# lumVoiture.net
KiCad netlist of a schematic drawn in EAGLE
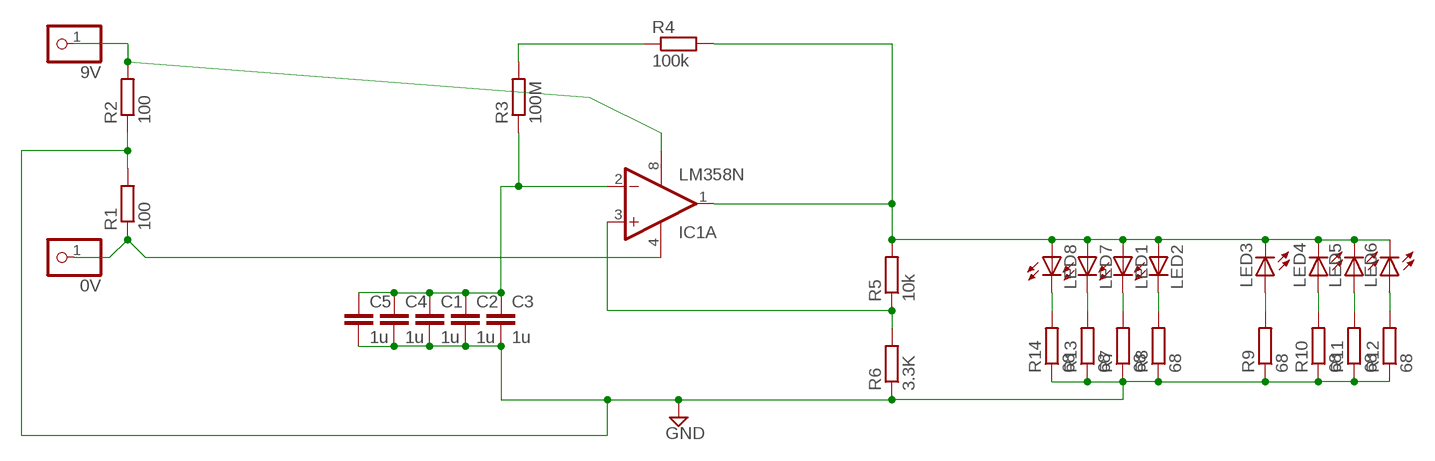
[diagram p0: schematic, sheet 1]

(export (version "E")
  (design (tool "Eeschema 10.0.6"))
  (components
    (comp (ref "0V")
      (value "PINHD-1X1")
      (footprint "eagle-import:1X01")
      (libsource (lib "eagle-import") (part "PINHD-1X1"))
    )
    (comp (ref "9V")
      (value "PINHD-1X1")
      (footprint "eagle-import:1X01")
      (libsource (lib "eagle-import") (part "PINHD-1X1"))
    )
    (comp (ref "C1")
      (value "1u")
      (footprint "eagle-import:C025-025X050")
      (libsource (lib "eagle-import") (part "C-EU025-025X050"))
    )
    (comp (ref "C2")
      (value "1u")
      (footprint "eagle-import:C025-025X050")
      (libsource (lib "eagle-import") (part "C-EU025-025X050"))
    )
    (comp (ref "C3")
      (value "1u")
      (footprint "eagle-import:C025-025X050")
      (libsource (lib "eagle-import") (part "C-EU025-025X050"))
    )
    (comp (ref "C4")
      (value "1u")
      (footprint "eagle-import:C025-025X050")
      (libsource (lib "eagle-import") (part "C-EU025-025X050"))
    )
    (comp (ref "C5")
      (value "1u")
      (footprint "eagle-import:C025-025X050")
      (libsource (lib "eagle-import") (part "C-EU025-025X050"))
    )
    (comp (ref "IC1")
      (value "LM358N")
      (footprint "eagle-import:DIL08")
      (libsource (lib "eagle-import") (part "LM358N"))
    )
    (comp (ref "LED1")
      (value "LED5MM")
      (footprint "eagle-import:LED5MM")
      (libsource (lib "eagle-import") (part "LED5MM"))
    )
    (comp (ref "LED2")
      (value "LED5MM")
      (footprint "eagle-import:LED5MM")
      (libsource (lib "eagle-import") (part "LED5MM"))
    )
    (comp (ref "LED3")
      (value "LED5MM")
      (footprint "eagle-import:LED5MM")
      (libsource (lib "eagle-import") (part "LED5MM"))
    )
    (comp (ref "LED4")
      (value "LED5MM")
      (footprint "eagle-import:LED5MM")
      (libsource (lib "eagle-import") (part "LED5MM"))
    )
    (comp (ref "LED5")
      (value "LED5MM")
      (footprint "eagle-import:LED5MM")
      (libsource (lib "eagle-import") (part "LED5MM"))
    )
    (comp (ref "LED6")
      (value "LED5MM")
      (footprint "eagle-import:LED5MM")
      (libsource (lib "eagle-import") (part "LED5MM"))
    )
    (comp (ref "LED7")
      (value "LED5MM")
      (footprint "eagle-import:LED5MM")
      (libsource (lib "eagle-import") (part "LED5MM"))
    )
    (comp (ref "LED8")
      (value "LED5MM")
      (footprint "eagle-import:LED5MM")
      (libsource (lib "eagle-import") (part "LED5MM"))
    )
    (comp (ref "R1")
      (value "100")
      (footprint "eagle-import:0207_10")
      (libsource (lib "eagle-import") (part "R-EU_0207/10"))
    )
    (comp (ref "R2")
      (value "100")
      (footprint "eagle-import:0207_10")
      (libsource (lib "eagle-import") (part "R-EU_0207/10"))
    )
    (comp (ref "R3")
      (value "100M")
      (footprint "eagle-import:0207_10")
      (libsource (lib "eagle-import") (part "R-EU_0207/10"))
    )
    (comp (ref "R4")
      (value "100k")
      (footprint "eagle-import:0207_10")
      (libsource (lib "eagle-import") (part "R-EU_0207/10"))
    )
    (comp (ref "R5")
      (value "10k")
      (footprint "eagle-import:0207_10")
      (libsource (lib "eagle-import") (part "R-EU_0207/10"))
    )
    (comp (ref "R6")
      (value "3.3K")
      (footprint "eagle-import:0207_10")
      (libsource (lib "eagle-import") (part "R-EU_0207/10"))
    )
    (comp (ref "R7")
      (value "68")
      (footprint "eagle-import:0207_10")
      (libsource (lib "eagle-import") (part "R-EU_0207/10"))
    )
    (comp (ref "R8")
      (value "68")
      (footprint "eagle-import:0207_10")
      (libsource (lib "eagle-import") (part "R-EU_0207/10"))
    )
    (comp (ref "R9")
      (value "68")
      (footprint "eagle-import:0207_10")
      (libsource (lib "eagle-import") (part "R-EU_0207/10"))
    )
    (comp (ref "R10")
      (value "68")
      (footprint "eagle-import:0207_10")
      (libsource (lib "eagle-import") (part "R-EU_0207/10"))
    )
    (comp (ref "R11")
      (value "68")
      (footprint "eagle-import:0207_10")
      (libsource (lib "eagle-import") (part "R-EU_0207/10"))
    )
    (comp (ref "R12")
      (value "68")
      (footprint "eagle-import:0207_10")
      (libsource (lib "eagle-import") (part "R-EU_0207/10"))
    )
    (comp (ref "R13")
      (value "68")
      (footprint "eagle-import:0207_10")
      (libsource (lib "eagle-import") (part "R-EU_0207/10"))
    )
    (comp (ref "R14")
      (value "68")
      (footprint "eagle-import:0207_10")
      (libsource (lib "eagle-import") (part "R-EU_0207/10"))
    )
  )
  (nets
    (net (code "1") (name "GND") (class "Default")
      (node (ref "C1") (pin "2") (pinfunction "2_2") (pintype "passive"))
      (node (ref "C2") (pin "2") (pinfunction "2_2") (pintype "passive"))
      (node (ref "C3") (pin "2") (pinfunction "2_2") (pintype "passive"))
      (node (ref "C4") (pin "2") (pinfunction "2_2") (pintype "passive"))
      (node (ref "C5") (pin "2") (pinfunction "2_2") (pintype "passive"))
      (node (ref "R1") (pin "2") (pinfunction "2_2") (pintype "passive"))
      (node (ref "R10") (pin "1") (pinfunction "1_1") (pintype "passive"))
      (node (ref "R11") (pin "1") (pinfunction "1_1") (pintype "passive"))
      (node (ref "R12") (pin "1") (pinfunction "1_1") (pintype "passive"))
      (node (ref "R13") (pin "1") (pinfunction "1_1") (pintype "passive"))
      (node (ref "R14") (pin "1") (pinfunction "1_1") (pintype "passive"))
      (node (ref "R2") (pin "1") (pinfunction "1_1") (pintype "passive"))
      (node (ref "R6") (pin "1") (pinfunction "1_1") (pintype "passive"))
      (node (ref "R7") (pin "1") (pinfunction "1_1") (pintype "passive"))
      (node (ref "R8") (pin "1") (pinfunction "1_1") (pintype "passive"))
      (node (ref "R9") (pin "1") (pinfunction "1_1") (pintype "passive"))
    )
    (net (code "2") (name "Net-(IC1A-+IN)") (class "Default")
      (node (ref "IC1") (pin "3") (pinfunction "+IN_3") (pintype "input"))
      (node (ref "R5") (pin "1") (pinfunction "1_1") (pintype "passive"))
      (node (ref "R6") (pin "2") (pinfunction "2_2") (pintype "passive"))
    )
    (net (code "3") (name "Net-(IC1A--IN)") (class "Default")
      (node (ref "C1") (pin "1") (pinfunction "1_1") (pintype "passive"))
      (node (ref "C2") (pin "1") (pinfunction "1_1") (pintype "passive"))
      (node (ref "C3") (pin "1") (pinfunction "1_1") (pintype "passive"))
      (node (ref "C4") (pin "1") (pinfunction "1_1") (pintype "passive"))
      (node (ref "C5") (pin "1") (pinfunction "1_1") (pintype "passive"))
      (node (ref "IC1") (pin "2") (pinfunction "-IN_2") (pintype "input"))
      (node (ref "R3") (pin "1") (pinfunction "1_1") (pintype "passive"))
    )
    (net (code "4") (name "Net-(IC1A-OUT)") (class "Default")
      (node (ref "IC1") (pin "1") (pinfunction "OUT_1") (pintype "output"))
      (node (ref "LED1") (pin "A") (pinfunction "A_A") (pintype "passive"))
      (node (ref "LED2") (pin "A") (pinfunction "A_A") (pintype "passive"))
      (node (ref "LED3") (pin "K") (pinfunction "C_K") (pintype "passive"))
      (node (ref "LED4") (pin "K") (pinfunction "C_K") (pintype "passive"))
      (node (ref "LED5") (pin "K") (pinfunction "C_K") (pintype "passive"))
      (node (ref "LED6") (pin "K") (pinfunction "C_K") (pintype "passive"))
      (node (ref "LED7") (pin "A") (pinfunction "A_A") (pintype "passive"))
      (node (ref "LED8") (pin "A") (pinfunction "A_A") (pintype "passive"))
      (node (ref "R4") (pin "2") (pinfunction "2_2") (pintype "passive"))
      (node (ref "R5") (pin "2") (pinfunction "2_2") (pintype "passive"))
    )
    (net (code "5") (name "Net-(IC1C-V+)") (class "Default")
      (node (ref "9V") (pin "1") (pinfunction "1_1") (pintype "passive"))
      (node (ref "IC1") (pin "8") (pinfunction "V+_8") (pintype "power_in"))
      (node (ref "R2") (pin "2") (pinfunction "2_2") (pintype "passive"))
    )
    (net (code "6") (name "Net-(IC1C-V-)") (class "Default")
      (node (ref "0V") (pin "1") (pinfunction "1_1") (pintype "passive"))
      (node (ref "IC1") (pin "4") (pinfunction "V-_4") (pintype "power_in"))
      (node (ref "R1") (pin "1") (pinfunction "1_1") (pintype "passive"))
    )
    (net (code "7") (name "Net-(LED1-C)") (class "Default")
      (node (ref "LED1") (pin "K") (pinfunction "C_K") (pintype "passive"))
      (node (ref "R7") (pin "2") (pinfunction "2_2") (pintype "passive"))
    )
    (net (code "8") (name "Net-(LED2-C)") (class "Default")
      (node (ref "LED2") (pin "K") (pinfunction "C_K") (pintype "passive"))
      (node (ref "R8") (pin "2") (pinfunction "2_2") (pintype "passive"))
    )
    (net (code "9") (name "Net-(LED3-PadA)") (class "Default")
      (node (ref "LED3") (pin "A") (pinfunction "A_A") (pintype "passive"))
      (node (ref "R9") (pin "2") (pinfunction "2_2") (pintype "passive"))
    )
    (net (code "10") (name "Net-(LED4-PadA)") (class "Default")
      (node (ref "LED4") (pin "A") (pinfunction "A_A") (pintype "passive"))
      (node (ref "R10") (pin "2") (pinfunction "2_2") (pintype "passive"))
    )
    (net (code "11") (name "Net-(LED5-PadA)") (class "Default")
      (node (ref "LED5") (pin "A") (pinfunction "A_A") (pintype "passive"))
      (node (ref "R11") (pin "2") (pinfunction "2_2") (pintype "passive"))
    )
    (net (code "12") (name "Net-(LED6-PadA)") (class "Default")
      (node (ref "LED6") (pin "A") (pinfunction "A_A") (pintype "passive"))
      (node (ref "R12") (pin "2") (pinfunction "2_2") (pintype "passive"))
    )
    (net (code "13") (name "Net-(LED7-C)") (class "Default")
      (node (ref "LED7") (pin "K") (pinfunction "C_K") (pintype "passive"))
      (node (ref "R13") (pin "2") (pinfunction "2_2") (pintype "passive"))
    )
    (net (code "14") (name "Net-(LED8-C)") (class "Default")
      (node (ref "LED8") (pin "K") (pinfunction "C_K") (pintype "passive"))
      (node (ref "R14") (pin "2") (pinfunction "2_2") (pintype "passive"))
    )
    (net (code "15") (name "Net-(R3-Pad2)") (class "Default")
      (node (ref "R3") (pin "2") (pinfunction "2_2") (pintype "passive"))
      (node (ref "R4") (pin "1") (pinfunction "1_1") (pintype "passive"))
    )
  )
)
